# ADCRead.net
KiCad netlist of a schematic drawn in Altium Designer
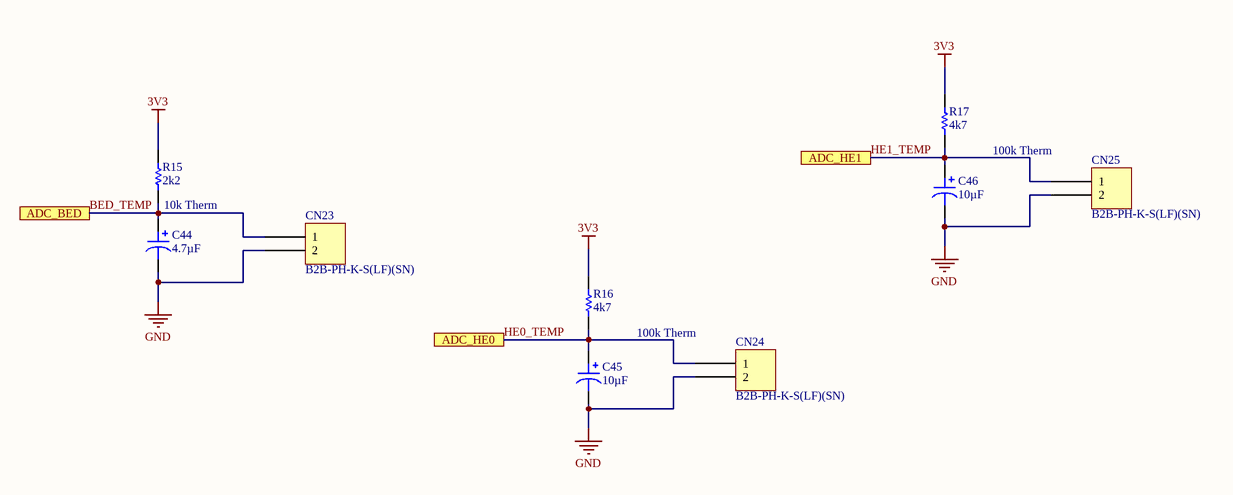
[diagram p0: ADCRead.SchDoc]

(export (version "E")
  (design (tool "Eeschema 10.0.6"))
  (components
    (comp (ref "C44")
      (value "4.7µF")
      (footprint "CAP ALSMD POLY 4.3MM H5.5MM")
      (description "CAP ALUM POLY 4.7UF 20% 10V SMD")
      (fields (field (name "PART NUMBER") "PCF1A4R7MCL1GB") (field (name "MANUFACTURER") "Nichicon"))
      (libsource (lib "Celestial Altium Library - altium_library") (part "Polarised Capacitor"))
    )
    (comp (ref "C45")
      (value "10µF")
      (footprint "CAP ALSMD 5.3MM H5.4MM")
      (description "CAP ALUM 10UF 20% 16V SMD")
      (fields (field (name "PART NUMBER") "UZP1C100MCL1GB") (field (name "MANUFACTURER") "Nichicon"))
      (libsource (lib "Celestial Altium Library - altium_library") (part "Polarised Capacitor"))
    )
    (comp (ref "C46")
      (value "10µF")
      (footprint "CAP ALSMD 5.3MM H5.4MM")
      (description "CAP ALUM 10UF 20% 16V SMD")
      (fields (field (name "PART NUMBER") "UZP1C100MCL1GB") (field (name "MANUFACTURER") "Nichicon"))
      (libsource (lib "Celestial Altium Library - altium_library") (part "Polarised Capacitor"))
    )
    (comp (ref "CN23")
      (value "B2B-PH-K-S(LF)(SN)")
      (footprint "JST B2B-PH-K")
      (description "CONN HEADER VERT 2POS 2MM")
      (fields (field (name "MANUFACTURER") "JST Sales America Inc."))
      (libsource (lib "Celestial Altium Library - altium_library") (part "2 Pin"))
    )
    (comp (ref "CN24")
      (value "B2B-PH-K-S(LF)(SN)")
      (footprint "JST B2B-PH-K")
      (description "CONN HEADER VERT 2POS 2MM")
      (fields (field (name "MANUFACTURER") "JST Sales America Inc."))
      (libsource (lib "Celestial Altium Library - altium_library") (part "2 Pin"))
    )
    (comp (ref "CN25")
      (value "B2B-PH-K-S(LF)(SN)")
      (footprint "JST B2B-PH-K")
      (description "CONN HEADER VERT 2POS 2MM")
      (fields (field (name "MANUFACTURER") "JST Sales America Inc."))
      (libsource (lib "Celestial Altium Library - altium_library") (part "2 Pin"))
    )
    (comp (ref "R15")
      (value "2k2")
      (footprint "1608[0603]")
      (description "Resistor")
      (fields (field (name "Comment") "Res1") (field (name "PUBLISHER") "Altium Limited"))
      (libsource (lib "Miscellaneous Devices") (part "Res1"))
    )
    (comp (ref "R16")
      (value "4k7")
      (footprint "1608[0603]")
      (description "Resistor")
      (fields (field (name "Comment") "Res1") (field (name "PUBLISHER") "Altium Limited"))
      (libsource (lib "Miscellaneous Devices") (part "Res1"))
    )
    (comp (ref "R17")
      (value "4k7")
      (footprint "1608[0603]")
      (description "Resistor")
      (fields (field (name "Comment") "Res1") (field (name "PUBLISHER") "Altium Limited"))
      (libsource (lib "Miscellaneous Devices") (part "Res1"))
    )
  )
  (nets
    (net (code "1") (name "/BED_TEMP") (class "Default")
      (node (ref "C44") (pin "1") (pinfunction "1_1") (pintype "passive"))
      (node (ref "CN23") (pin "1") (pinfunction "1_1") (pintype "passive"))
      (node (ref "R15") (pin "2") (pinfunction "2_2") (pintype "passive"))
    )
    (net (code "2") (name "/HE0_TEMP") (class "Default")
      (node (ref "C45") (pin "1") (pinfunction "1_1") (pintype "passive"))
      (node (ref "CN24") (pin "1") (pinfunction "1_1") (pintype "passive"))
      (node (ref "R16") (pin "2") (pinfunction "2_2") (pintype "passive"))
    )
    (net (code "3") (name "/HE1_TEMP") (class "Default")
      (node (ref "C46") (pin "1") (pinfunction "1_1") (pintype "passive"))
      (node (ref "CN25") (pin "1") (pinfunction "1_1") (pintype "passive"))
      (node (ref "R17") (pin "2") (pinfunction "2_2") (pintype "passive"))
    )
    (net (code "4") (name "3V3") (class "Default")
      (node (ref "R15") (pin "1") (pinfunction "1_1") (pintype "passive"))
      (node (ref "R16") (pin "1") (pinfunction "1_1") (pintype "passive"))
      (node (ref "R17") (pin "1") (pinfunction "1_1") (pintype "passive"))
    )
    (net (code "5") (name "GND") (class "Default")
      (node (ref "C44") (pin "2") (pinfunction "2_2") (pintype "passive"))
      (node (ref "C45") (pin "2") (pinfunction "2_2") (pintype "passive"))
      (node (ref "C46") (pin "2") (pinfunction "2_2") (pintype "passive"))
      (node (ref "CN23") (pin "2") (pinfunction "2_2") (pintype "passive"))
      (node (ref "CN24") (pin "2") (pinfunction "2_2") (pintype "passive"))
      (node (ref "CN25") (pin "2") (pinfunction "2_2") (pintype "passive"))
    )
  )
)
